# signal-tower.net
KiCad netlist of a schematic drawn in EAGLE
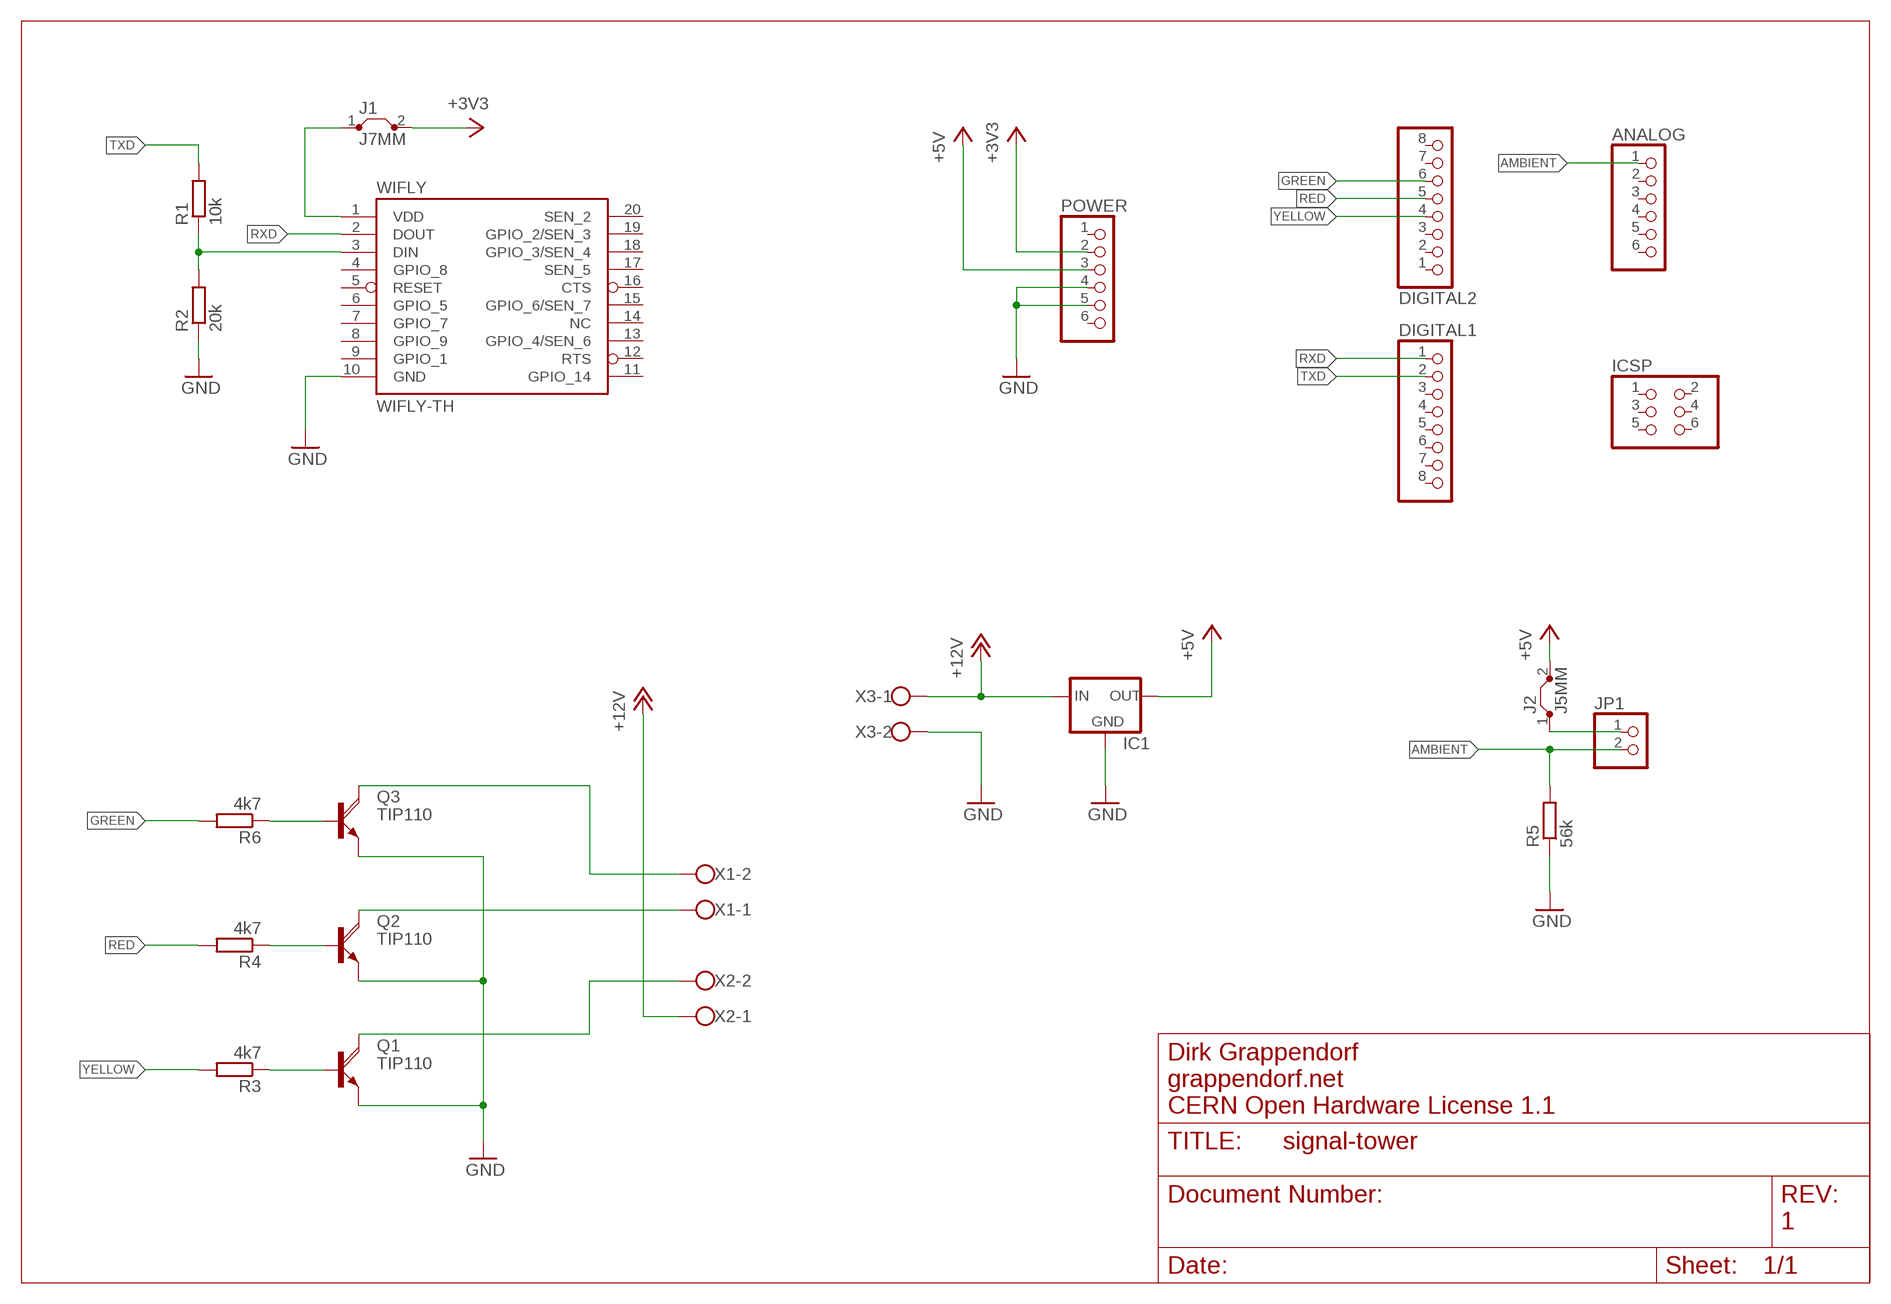
[diagram p0: schematic, sheet 1]

(export (version "E")
  (design (tool "Eeschema 10.0.6"))
  (components
    (comp (ref "ANALOG")
      (value "PINHD-1X6")
      (footprint "eagle-import:1X06")
      (libsource (lib "eagle-import") (part "PINHD-1X6"))
    )
    (comp (ref "DIGITAL1")
      (value "PINHD-1X8TH")
      (footprint "eagle-import:1X08-TH")
      (libsource (lib "eagle-import") (part "PINHD-1X8TH"))
    )
    (comp (ref "DIGITAL2")
      (value "PINHD-1X8_2.54")
      (footprint "eagle-import:1X08")
      (libsource (lib "eagle-import") (part "PINHD-1X8_2.54"))
    )
    (comp (ref "IC1")
      (value "78XXS")
      (footprint "eagle-import:78XXS")
      (libsource (lib "eagle-import") (part "78XXS"))
    )
    (comp (ref "ICSP")
      (value "PINHD-2X3")
      (footprint "eagle-import:2X03")
      (libsource (lib "eagle-import") (part "PINHD-2X3"))
    )
    (comp (ref "J1")
      (value "J7MM")
      (footprint "eagle-import:07")
      (libsource (lib "eagle-import") (part "J7MM"))
    )
    (comp (ref "J2")
      (value "J5MM")
      (footprint "eagle-import:05")
      (libsource (lib "eagle-import") (part "J5MM"))
    )
    (comp (ref "JP1")
      (value "PINHD-1X2")
      (footprint "eagle-import:1X02")
      (libsource (lib "eagle-import") (part "PINHD-1X2"))
    )
    (comp (ref "POWER")
      (value "PINHD-1X6_2.54")
      (footprint "eagle-import:1X06")
      (libsource (lib "eagle-import") (part "PINHD-1X6_2.54"))
    )
    (comp (ref "Q1")
      (value "TIP110")
      (footprint "eagle-import:TO220BV")
      (libsource (lib "eagle-import") (part "TIP110"))
    )
    (comp (ref "Q2")
      (value "TIP110")
      (footprint "eagle-import:TO220BV")
      (libsource (lib "eagle-import") (part "TIP110"))
    )
    (comp (ref "Q3")
      (value "TIP110")
      (footprint "eagle-import:TO220BV")
      (libsource (lib "eagle-import") (part "TIP110"))
    )
    (comp (ref "R1")
      (value "10k")
      (footprint "eagle-import:0204_7")
      (libsource (lib "eagle-import") (part "R-EU_0204/7"))
    )
    (comp (ref "R2")
      (value "20k")
      (footprint "eagle-import:0204_7")
      (libsource (lib "eagle-import") (part "R-EU_0204/7"))
    )
    (comp (ref "R3")
      (value "4k7")
      (footprint "eagle-import:0204_7")
      (libsource (lib "eagle-import") (part "R-EU_0204/7"))
    )
    (comp (ref "R4")
      (value "4k7")
      (footprint "eagle-import:0204_7")
      (libsource (lib "eagle-import") (part "R-EU_0204/7"))
    )
    (comp (ref "R5")
      (value "56k")
      (footprint "eagle-import:0204_7")
      (libsource (lib "eagle-import") (part "R-EU_0204/7"))
    )
    (comp (ref "R6")
      (value "4k7")
      (footprint "eagle-import:0204_7")
      (libsource (lib "eagle-import") (part "R-EU_0204/7"))
    )
    (comp (ref "WIFLY")
      (value "WIFLY-TH")
      (footprint "eagle-import:WIFLY-TH")
      (libsource (lib "eagle-import") (part "WIFLY-TH"))
    )
    (comp (ref "X1")
      (value "W237-102")
      (footprint "eagle-import:W237-102")
      (fields (field (name "MPN") "237-102"))
      (libsource (lib "eagle-import") (part "W237-102"))
    )
    (comp (ref "X2")
      (value "W237-102")
      (footprint "eagle-import:W237-102")
      (fields (field (name "MPN") "237-102"))
      (libsource (lib "eagle-import") (part "W237-102"))
    )
    (comp (ref "X3")
      (value "W237-102")
      (footprint "eagle-import:W237-102")
      (fields (field (name "MPN") "237-102"))
      (libsource (lib "eagle-import") (part "W237-102"))
    )
  )
  (nets
    (net (code "1") (name "+3V3") (class "Default")
      (node (ref "J1") (pin "2") (pinfunction "2_2") (pintype "passive"))
      (node (ref "POWER") (pin "2") (pinfunction "2_2") (pintype "passive"))
    )
    (net (code "2") (name "+5V") (class "Default")
      (node (ref "IC1") (pin "OUT") (pinfunction "OUT_OUT") (pintype "passive"))
      (node (ref "J2") (pin "2") (pinfunction "2_2") (pintype "passive"))
      (node (ref "POWER") (pin "3") (pinfunction "3_3") (pintype "passive"))
    )
    (net (code "3") (name "+12V") (class "Default")
      (node (ref "IC1") (pin "IN") (pinfunction "IN_IN") (pintype "input"))
      (node (ref "X2") (pin "1") (pinfunction "KL_1") (pintype "passive"))
      (node (ref "X3") (pin "1") (pinfunction "KL_1") (pintype "passive"))
    )
    (net (code "4") (name "AMBIENT") (class "Default")
      (node (ref "ANALOG") (pin "1") (pinfunction "1_1") (pintype "passive"))
      (node (ref "JP1") (pin "2") (pinfunction "2_2") (pintype "passive"))
      (node (ref "R5") (pin "2") (pinfunction "2_2") (pintype "passive"))
    )
    (net (code "5") (name "GND") (class "Default")
      (node (ref "IC1") (pin "GND") (pinfunction "GND_GND") (pintype "input"))
      (node (ref "POWER") (pin "4") (pinfunction "4_4") (pintype "passive"))
      (node (ref "POWER") (pin "5") (pinfunction "5_5") (pintype "passive"))
      (node (ref "Q1") (pin "S") (pinfunction "E_S") (pintype "passive"))
      (node (ref "Q2") (pin "S") (pinfunction "E_S") (pintype "passive"))
      (node (ref "Q3") (pin "S") (pinfunction "E_S") (pintype "passive"))
      (node (ref "R2") (pin "1") (pinfunction "1_1") (pintype "passive"))
      (node (ref "R5") (pin "1") (pinfunction "1_1") (pintype "passive"))
      (node (ref "WIFLY") (pin "10") (pinfunction "GND_10") (pintype "power_in"))
      (node (ref "X3") (pin "2") (pinfunction "KL_2") (pintype "passive"))
    )
    (net (code "6") (name "GREEN") (class "Default")
      (node (ref "DIGITAL2") (pin "6") (pinfunction "6_6") (pintype "passive"))
      (node (ref "R6") (pin "2") (pinfunction "2_2") (pintype "passive"))
    )
    (net (code "7") (name "Net-(J2-Pad1)") (class "Default")
      (node (ref "J2") (pin "1") (pinfunction "1_1") (pintype "passive"))
      (node (ref "JP1") (pin "1") (pinfunction "1_1") (pintype "passive"))
    )
    (net (code "8") (name "Net-(Q1-B)") (class "Default")
      (node (ref "Q1") (pin "G") (pinfunction "B_G") (pintype "passive"))
      (node (ref "R3") (pin "1") (pinfunction "1_1") (pintype "passive"))
    )
    (net (code "9") (name "Net-(Q1-C)") (class "Default")
      (node (ref "Q1") (pin "D") (pinfunction "C_D") (pintype "passive"))
      (node (ref "X2") (pin "2") (pinfunction "KL_2") (pintype "passive"))
    )
    (net (code "10") (name "Net-(Q2-B)") (class "Default")
      (node (ref "Q2") (pin "G") (pinfunction "B_G") (pintype "passive"))
      (node (ref "R4") (pin "1") (pinfunction "1_1") (pintype "passive"))
    )
    (net (code "11") (name "Net-(Q2-C)") (class "Default")
      (node (ref "Q2") (pin "D") (pinfunction "C_D") (pintype "passive"))
      (node (ref "X1") (pin "1") (pinfunction "KL_1") (pintype "passive"))
    )
    (net (code "12") (name "Net-(Q3-B)") (class "Default")
      (node (ref "Q3") (pin "G") (pinfunction "B_G") (pintype "passive"))
      (node (ref "R6") (pin "1") (pinfunction "1_1") (pintype "passive"))
    )
    (net (code "13") (name "Net-(Q3-C)") (class "Default")
      (node (ref "Q3") (pin "D") (pinfunction "C_D") (pintype "passive"))
      (node (ref "X1") (pin "2") (pinfunction "KL_2") (pintype "passive"))
    )
    (net (code "14") (name "Net-(WIFLY-DIN)") (class "Default")
      (node (ref "R1") (pin "1") (pinfunction "1_1") (pintype "passive"))
      (node (ref "R2") (pin "2") (pinfunction "2_2") (pintype "passive"))
      (node (ref "WIFLY") (pin "3") (pinfunction "DIN_3") (pintype "input"))
    )
    (net (code "15") (name "Net-(WIFLY-VDD)") (class "Default")
      (node (ref "J1") (pin "1") (pinfunction "1_1") (pintype "passive"))
      (node (ref "WIFLY") (pin "1") (pinfunction "VDD_1") (pintype "power_in"))
    )
    (net (code "16") (name "RED") (class "Default")
      (node (ref "DIGITAL2") (pin "5") (pinfunction "5_5") (pintype "passive"))
      (node (ref "R4") (pin "2") (pinfunction "2_2") (pintype "passive"))
    )
    (net (code "17") (name "RXD") (class "Default")
      (node (ref "DIGITAL1") (pin "1") (pinfunction "1_1") (pintype "passive"))
      (node (ref "WIFLY") (pin "2") (pinfunction "DOUT_2") (pintype "output"))
    )
    (net (code "18") (name "TXD") (class "Default")
      (node (ref "DIGITAL1") (pin "2") (pinfunction "2_2") (pintype "passive"))
      (node (ref "R1") (pin "2") (pinfunction "2_2") (pintype "passive"))
    )
    (net (code "19") (name "YELLOW") (class "Default")
      (node (ref "DIGITAL2") (pin "4") (pinfunction "4_4") (pintype "passive"))
      (node (ref "R3") (pin "2") (pinfunction "2_2") (pintype "passive"))
    )
    (net (code "20") (name "unconnected-(ANALOG-Pad2)") (class "Default")
      (node (ref "ANALOG") (pin "2") (pinfunction "2_2") (pintype "passive"))
    )
    (net (code "21") (name "unconnected-(ANALOG-Pad3)") (class "Default")
      (node (ref "ANALOG") (pin "3") (pinfunction "3_3") (pintype "passive"))
    )
    (net (code "22") (name "unconnected-(ANALOG-Pad4)") (class "Default")
      (node (ref "ANALOG") (pin "4") (pinfunction "4_4") (pintype "passive"))
    )
    (net (code "23") (name "unconnected-(ANALOG-Pad5)") (class "Default")
      (node (ref "ANALOG") (pin "5") (pinfunction "5_5") (pintype "passive"))
    )
    (net (code "24") (name "unconnected-(ANALOG-Pad6)") (class "Default")
      (node (ref "ANALOG") (pin "6") (pinfunction "6_6") (pintype "passive"))
    )
    (net (code "25") (name "unconnected-(DIGITAL1-Pad3)") (class "Default")
      (node (ref "DIGITAL1") (pin "3") (pinfunction "3_3") (pintype "passive"))
    )
    (net (code "26") (name "unconnected-(DIGITAL1-Pad4)") (class "Default")
      (node (ref "DIGITAL1") (pin "4") (pinfunction "4_4") (pintype "passive"))
    )
    (net (code "27") (name "unconnected-(DIGITAL1-Pad5)") (class "Default")
      (node (ref "DIGITAL1") (pin "5") (pinfunction "5_5") (pintype "passive"))
    )
    (net (code "28") (name "unconnected-(DIGITAL1-Pad6)") (class "Default")
      (node (ref "DIGITAL1") (pin "6") (pinfunction "6_6") (pintype "passive"))
    )
    (net (code "29") (name "unconnected-(DIGITAL1-Pad7)") (class "Default")
      (node (ref "DIGITAL1") (pin "7") (pinfunction "7_7") (pintype "passive"))
    )
    (net (code "30") (name "unconnected-(DIGITAL1-Pad8)") (class "Default")
      (node (ref "DIGITAL1") (pin "8") (pinfunction "8_8") (pintype "passive"))
    )
    (net (code "31") (name "unconnected-(DIGITAL2-Pad1)") (class "Default")
      (node (ref "DIGITAL2") (pin "1") (pinfunction "1_1") (pintype "passive"))
    )
    (net (code "32") (name "unconnected-(DIGITAL2-Pad2)") (class "Default")
      (node (ref "DIGITAL2") (pin "2") (pinfunction "2_2") (pintype "passive"))
    )
    (net (code "33") (name "unconnected-(DIGITAL2-Pad3)") (class "Default")
      (node (ref "DIGITAL2") (pin "3") (pinfunction "3_3") (pintype "passive"))
    )
    (net (code "34") (name "unconnected-(DIGITAL2-Pad7)") (class "Default")
      (node (ref "DIGITAL2") (pin "7") (pinfunction "7_7") (pintype "passive"))
    )
    (net (code "35") (name "unconnected-(DIGITAL2-Pad8)") (class "Default")
      (node (ref "DIGITAL2") (pin "8") (pinfunction "8_8") (pintype "passive"))
    )
    (net (code "36") (name "unconnected-(ICSP-Pad1)") (class "Default")
      (node (ref "ICSP") (pin "1") (pinfunction "1_1") (pintype "passive"))
    )
    (net (code "37") (name "unconnected-(ICSP-Pad2)") (class "Default")
      (node (ref "ICSP") (pin "2") (pinfunction "2_2") (pintype "passive"))
    )
    (net (code "38") (name "unconnected-(ICSP-Pad3)") (class "Default")
      (node (ref "ICSP") (pin "3") (pinfunction "3_3") (pintype "passive"))
    )
    (net (code "39") (name "unconnected-(ICSP-Pad4)") (class "Default")
      (node (ref "ICSP") (pin "4") (pinfunction "4_4") (pintype "passive"))
    )
    (net (code "40") (name "unconnected-(ICSP-Pad5)") (class "Default")
      (node (ref "ICSP") (pin "5") (pinfunction "5_5") (pintype "passive"))
    )
    (net (code "41") (name "unconnected-(ICSP-Pad6)") (class "Default")
      (node (ref "ICSP") (pin "6") (pinfunction "6_6") (pintype "passive"))
    )
    (net (code "42") (name "unconnected-(POWER-Pad1)") (class "Default")
      (node (ref "POWER") (pin "1") (pinfunction "1_1") (pintype "passive"))
    )
    (net (code "43") (name "unconnected-(POWER-Pad6)") (class "Default")
      (node (ref "POWER") (pin "6") (pinfunction "6_6") (pintype "passive"))
    )
    (net (code "44") (name "unconnected-(WIFLY-CTS-Pad16)") (class "Default")
      (node (ref "WIFLY") (pin "16") (pinfunction "CTS_16") (pintype "input"))
    )
    (net (code "45") (name "unconnected-(WIFLY-GPIO_1-Pad9)") (class "Default")
      (node (ref "WIFLY") (pin "9") (pinfunction "GPIO_1_9") (pintype "bidirectional"))
    )
    (net (code "46") (name "unconnected-(WIFLY-GPIO_2{slash}SEN_3-Pad19)") (class "Default")
      (node (ref "WIFLY") (pin "19") (pinfunction "GPIO_2/SEN_3_19") (pintype "bidirectional"))
    )
    (net (code "47") (name "unconnected-(WIFLY-GPIO_3{slash}SEN_4-Pad18)") (class "Default")
      (node (ref "WIFLY") (pin "18") (pinfunction "GPIO_3/SEN_4_18") (pintype "bidirectional"))
    )
    (net (code "48") (name "unconnected-(WIFLY-GPIO_4{slash}SEN_6-Pad13)") (class "Default")
      (node (ref "WIFLY") (pin "13") (pinfunction "GPIO_4/SEN_6_13") (pintype "bidirectional"))
    )
    (net (code "49") (name "unconnected-(WIFLY-GPIO_5-Pad6)") (class "Default")
      (node (ref "WIFLY") (pin "6") (pinfunction "GPIO_5_6") (pintype "bidirectional"))
    )
    (net (code "50") (name "unconnected-(WIFLY-GPIO_6{slash}SEN_7-Pad15)") (class "Default")
      (node (ref "WIFLY") (pin "15") (pinfunction "GPIO_6/SEN_7_15") (pintype "bidirectional"))
    )
    (net (code "51") (name "unconnected-(WIFLY-GPIO_7-Pad7)") (class "Default")
      (node (ref "WIFLY") (pin "7") (pinfunction "GPIO_7_7") (pintype "bidirectional"))
    )
    (net (code "52") (name "unconnected-(WIFLY-GPIO_8-Pad4)") (class "Default")
      (node (ref "WIFLY") (pin "4") (pinfunction "GPIO_8_4") (pintype "bidirectional"))
    )
    (net (code "53") (name "unconnected-(WIFLY-GPIO_9-Pad8)") (class "Default")
      (node (ref "WIFLY") (pin "8") (pinfunction "GPIO_9_8") (pintype "bidirectional"))
    )
    (net (code "54") (name "unconnected-(WIFLY-GPIO_14-Pad11)") (class "Default")
      (node (ref "WIFLY") (pin "11") (pinfunction "GPIO_14_11") (pintype "bidirectional"))
    )
    (net (code "55") (name "unconnected-(WIFLY-NC-Pad14)") (class "Default")
      (node (ref "WIFLY") (pin "14") (pinfunction "NC_14") (pintype "bidirectional"))
    )
    (net (code "56") (name "unconnected-(WIFLY-RESET-Pad5)") (class "Default")
      (node (ref "WIFLY") (pin "5") (pinfunction "RESET_5") (pintype "input"))
    )
    (net (code "57") (name "unconnected-(WIFLY-RTS-Pad12)") (class "Default")
      (node (ref "WIFLY") (pin "12") (pinfunction "RTS_12") (pintype "output"))
    )
    (net (code "58") (name "unconnected-(WIFLY-SEN_2-Pad20)") (class "Default")
      (node (ref "WIFLY") (pin "20") (pinfunction "SEN_2_20") (pintype "bidirectional"))
    )
    (net (code "59") (name "unconnected-(WIFLY-SEN_5-Pad17)") (class "Default")
      (node (ref "WIFLY") (pin "17") (pinfunction "SEN_5_17") (pintype "bidirectional"))
    )
  )
)
